# 3V-Switcher-50mA.net
KiCad netlist of a schematic drawn in Altium Designer
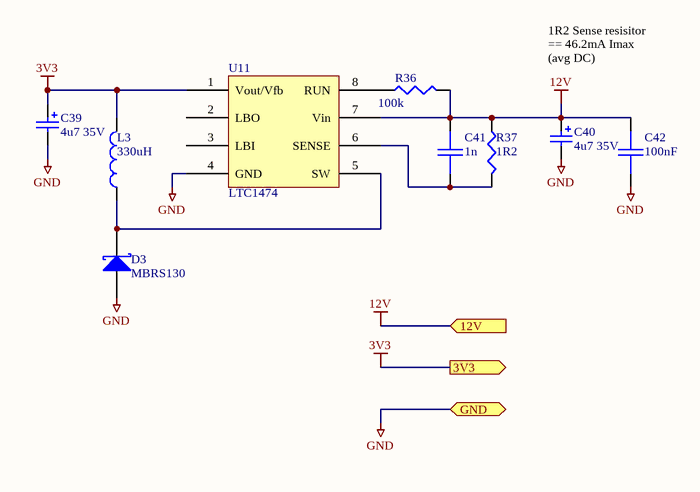
[diagram p0: 3V-Switcher-50mA.SchDoc]

(export (version "E")
  (design (tool "Eeschema 10.0.6"))
  (components
    (comp (ref "C39")
      (value "4u7 35V")
      (footprint "MCCT-CASEC")
      (description "Polarized Capacitor (Surface Mount)")
      (libsource (lib "Miscellaneous Devices") (part "Cap Pol3"))
    )
    (comp (ref "C40")
      (value "4u7 35V")
      (footprint "MCCT-CASEC")
      (description "Polarized Capacitor (Surface Mount)")
      (libsource (lib "Miscellaneous Devices") (part "Cap Pol3"))
    )
    (comp (ref "C41")
      (value "1n")
      (footprint "0603")
      (description "Capacitor")
      (libsource (lib "Miscellaneous Devices") (part "CAP"))
    )
    (comp (ref "C42")
      (value "100nF")
      (footprint "0603")
      (description "Capacitor")
      (libsource (lib "Miscellaneous Devices") (part "CAP"))
    )
    (comp (ref "D3")
      (value "MBRS130")
      (footprint "SMB")
      (description "Schottky Diode")
      (libsource (lib "RCLDQ") (part "D SCHOTTKY"))
    )
    (comp (ref "L3")
      (value "330uH")
      (footprint "1812")
      (description "Inductor")
      (libsource (lib "Miscellaneous Devices") (part "Inductor"))
    )
    (comp (ref "R36")
      (value "100k")
      (footprint "0603")
      (description "Resistor")
      (libsource (lib "RCLDQ") (part "RES1"))
    )
    (comp (ref "R37")
      (value "1R2")
      (footprint "0603")
      (description "Resistor")
      (libsource (lib "Miscellaneous Devices") (part "RES1"))
    )
    (comp (ref "U11")
      (value "LTC1474")
      (footprint "SO8")
      (description "Step-down converter")
      (libsource (lib "MiscellaneousIC") (part "LTC1474"))
    )
  )
  (nets
    (net (code "1") (name "3V3") (class "Default")
      (node (ref "C39") (pin "1") (pinfunction "1_1") (pintype "passive"))
      (node (ref "L3") (pin "2") (pinfunction "2_2") (pintype "passive"))
      (node (ref "U11") (pin "1") (pinfunction "Vout/Vfb_1") (pintype "passive"))
    )
    (net (code "2") (name "12V") (class "Default")
      (node (ref "C40") (pin "1") (pinfunction "1_1") (pintype "passive"))
      (node (ref "C41") (pin "1") (pinfunction "1_1") (pintype "passive"))
      (node (ref "C42") (pin "1") (pinfunction "1_1") (pintype "passive"))
      (node (ref "R36") (pin "2") (pinfunction "2_2") (pintype "passive"))
      (node (ref "R37") (pin "1") (pinfunction "1_1") (pintype "passive"))
      (node (ref "U11") (pin "7") (pinfunction "Vin_7") (pintype "passive"))
    )
    (net (code "3") (name "GND") (class "Default")
      (node (ref "C39") (pin "2") (pinfunction "2_2") (pintype "passive"))
      (node (ref "C40") (pin "2") (pinfunction "2_2") (pintype "passive"))
      (node (ref "C42") (pin "2") (pinfunction "2_2") (pintype "passive"))
      (node (ref "D3") (pin "A") (pinfunction "A_A") (pintype "passive"))
      (node (ref "U11") (pin "4") (pinfunction "GND_4") (pintype "passive"))
    )
    (net (code "4") (name "Net-(U11-RUN)") (class "Default")
      (node (ref "R36") (pin "1") (pinfunction "1_1") (pintype "passive"))
      (node (ref "U11") (pin "8") (pinfunction "RUN_8") (pintype "passive"))
    )
    (net (code "5") (name "Net-(U11-SENSE)") (class "Default")
      (node (ref "C41") (pin "2") (pinfunction "2_2") (pintype "passive"))
      (node (ref "R37") (pin "2") (pinfunction "2_2") (pintype "passive"))
      (node (ref "U11") (pin "6") (pinfunction "SENSE_6") (pintype "passive"))
    )
    (net (code "6") (name "Net-(U11-SW)") (class "Default")
      (node (ref "D3") (pin "K") (pinfunction "K_K") (pintype "passive"))
      (node (ref "L3") (pin "1") (pinfunction "1_1") (pintype "passive"))
      (node (ref "U11") (pin "5") (pinfunction "SW_5") (pintype "passive"))
    )
    (net (code "7") (name "unconnected-(U11-LBI-Pad3)") (class "Default")
      (node (ref "U11") (pin "3") (pinfunction "LBI_3") (pintype "passive"))
    )
    (net (code "8") (name "unconnected-(U11-LBO-Pad2)") (class "Default")
      (node (ref "U11") (pin "2") (pinfunction "LBO_2") (pintype "passive"))
    )
  )
)
